# P3V3_PP5V_GESTION.net
KiCad netlist of a schematic drawn in Altium Designer
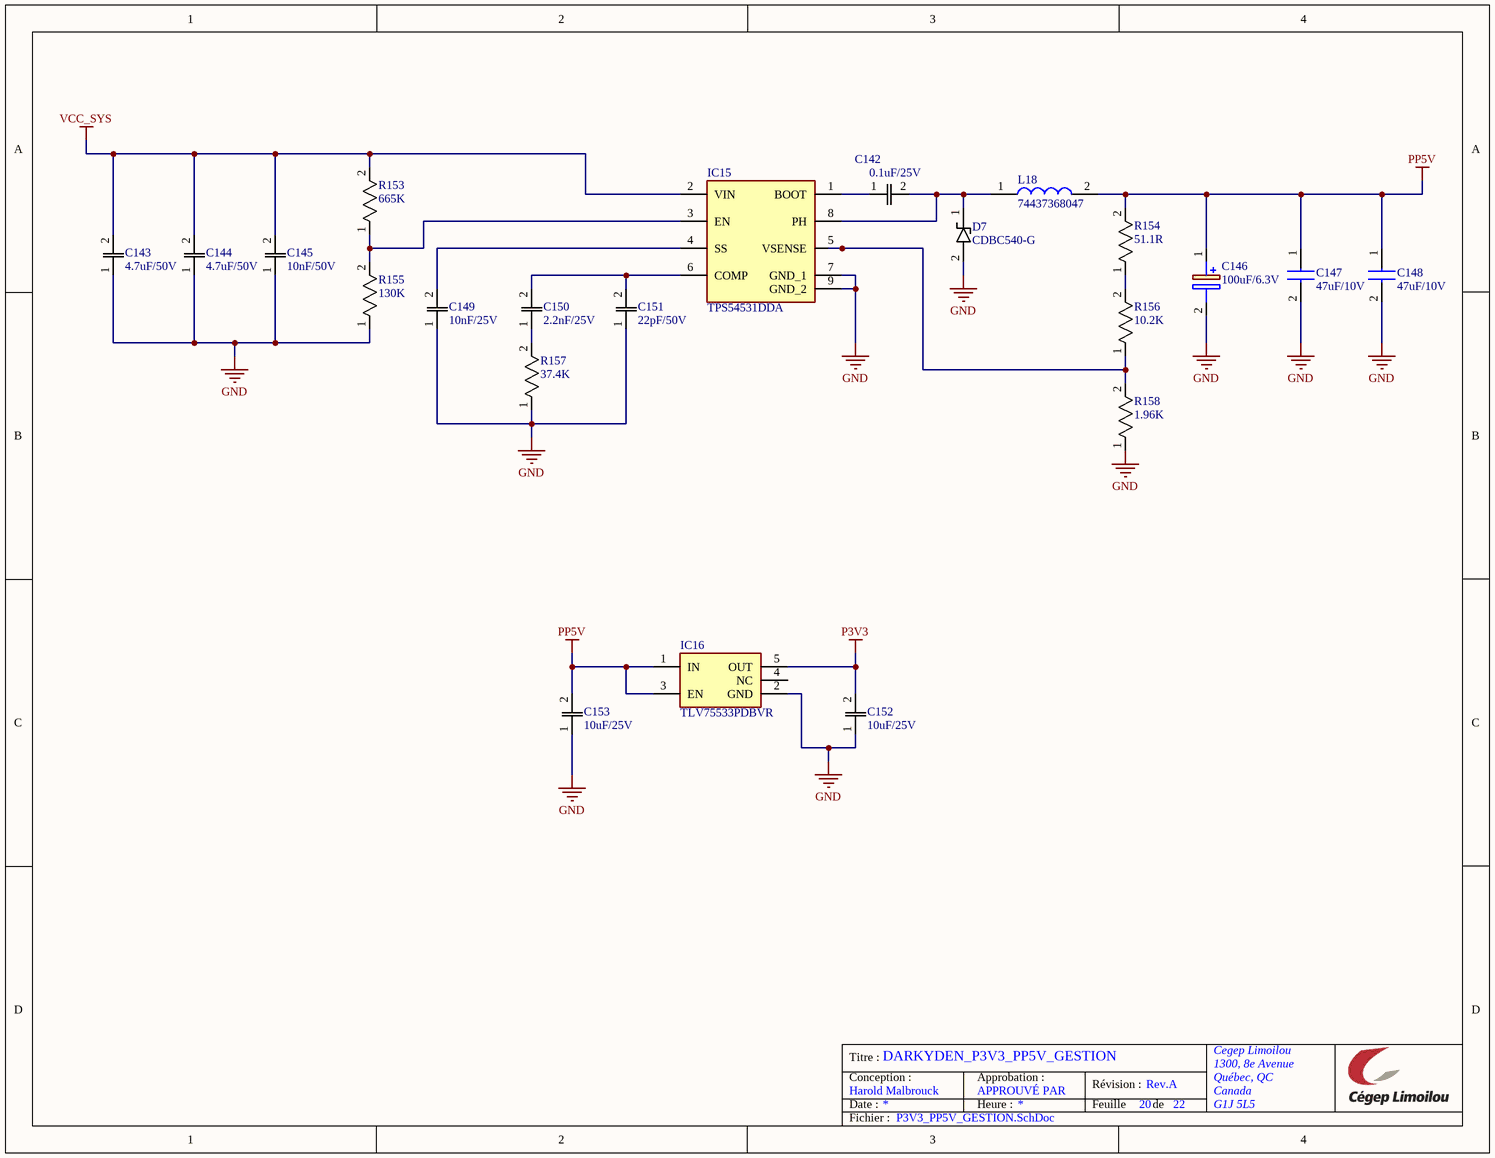
[diagram p0: P3V3_PP5V_GESTION.SchDoc]

(export (version "E")
  (design (tool "Eeschema 10.0.6"))
  (components
    (comp (ref "C142")
      (value "0.1uF/25V")
      (footprint "CAPC220145_88N_KEM")
      (description "0.1uF 25V X7R 10% SMD 0805 125C Plastic T/R")
      (fields
        (field (name "MANUFACTURER") "KEMET")
        (field (name "MANUFACTURER PART NUMBER") "C0805C104K3RACTU")
      )
      (libsource (lib "C0805C104K3RACTU") (part "C0805C104K3RACTU"))
    )
    (comp (ref "C143")
      (value "4.7uF/50V")
      (footprint "CAP_2012_TDK")
      (description "4.7uF/50V X5R 卤10% 0805 Multilayer Ceramic Capacitors MLCC - SMD/SMT ROHS")
      (fields
        (field (name "MANUFACTURER") "TDK")
        (field (name "MANUFACTURER PART NUMBER") "CGA4J3X5R1H475K125AB")
      )
      (libsource (lib "CGA4J3X5R1H475K125AB") (part "CGA4J3X5R1H475K125AB"))
    )
    (comp (ref "C144")
      (value "4.7uF/50V")
      (footprint "CAP_2012_TDK")
      (description "4.7uF/50V X5R 卤10% 0805 Multilayer Ceramic Capacitors MLCC - SMD/SMT ROHS")
      (fields
        (field (name "MANUFACTURER") "TDK")
        (field (name "MANUFACTURER PART NUMBER") "CGA4J3X5R1H475K125AB")
      )
      (libsource (lib "CGA4J3X5R1H475K125AB") (part "CGA4J3X5R1H475K125AB"))
    )
    (comp (ref "C145")
      (value "10nF/50V")
      (footprint "CAPC220145_88N_KEM")
      (description "10nF/50V X7R 0805 10%")
      (fields
        (field (name "MANUFACTURER") "KEMET")
        (field (name "MANUFACTURER PART NUMBER") "C0805C103K5RACTU")
      )
      (libsource (lib "C0805C103K5RACTU") (part "C0805C103K5RACTU"))
    )
    (comp (ref "C146")
      (value "100uF/6.3V")
      (footprint "SamacSys:T520B")
      (description "100uF / 6.3VDC B CASE 20%  Cap Tant Polymer SMD 3528-21 0.015 Ohm 105C T/R")
      (fields
        (field (name "MANUFACTURER_PART_NUMBER") "T520B107M006ATE015")
        (field (name "MOUSER PART NUMBER") "80-T520B107M6ATE15")
      )
      (libsource (lib "SamacSys") (part "T520B107M006ATE015"))
    )
    (comp (ref "C147")
      (value "47uF/10V")
      (footprint "SamacSys:CAPC3225X270N")
      (description "Multilayer Ceramic Capacitor, 47 uF, 10 V, ï¿½ 10%, X5R, 1210 [3225 Metric]")
      (fields
        (field (name "MANUFACTURER_PART_NUMBER") "GRM32ER61A476KE20L")
        (field (name "MOUSER PART NUMBER") "81-GRM32ER61A476KE20")
      )
      (libsource (lib "SamacSys") (part "GRM32ER61A476KE20L"))
    )
    (comp (ref "C148")
      (value "47uF/10V")
      (footprint "SamacSys:CAPC3225X270N")
      (description "Multilayer Ceramic Capacitor, 47 uF, 10 V, ï¿½ 10%, X5R, 1210 [3225 Metric]")
      (fields
        (field (name "MANUFACTURER_PART_NUMBER") "GRM32ER61A476KE20L")
        (field (name "MOUSER PART NUMBER") "81-GRM32ER61A476KE20")
      )
      (libsource (lib "SamacSys") (part "GRM32ER61A476KE20L"))
    )
    (comp (ref "C149")
      (value "10nF/25V")
      (footprint "SamacSys:C0805")
      (description "0.01uF 25V X7R 10% SMD 0805 125C Paper T/R")
      (fields
        (field (name "MANUFACTURER_PART_NUMBER") "C0805C103K3RACTU")
        (field (name "MOUSER PART NUMBER") "80-C0805C103K3R")
      )
      (libsource (lib "SamacSys") (part "C0805C103K3RACTU"))
    )
    (comp (ref "C150")
      (value "2.2nF/25V")
      (footprint "CAPC480350_110N_KEM")
      (description "2.2nF ±10% 25V Ceramic Capacitor C0G, NP0 0805 (2012 Metric)")
      (fields
        (field (name "MANUFACTURER") "KEMET")
        (field (name "MANUFACTURER PART NUMBER") "C0805C222K3GECTU")
      )
      (libsource (lib "C1812C222F1GACTU") (part "C0805C222K3GECTU"))
    )
    (comp (ref "C151")
      (value "22pF/50V")
      (footprint "CAPC220145_145N_KEM")
      (description "Cap Ceramic 22pF 50V X7R 5% Pad SMD 0805 125°C T/R")
      (fields
        (field (name "MANUFACTURER") "KEMET")
        (field (name "MANUFACTURER PART NUMBER") "C0805C220J5RACTU")
      )
      (libsource (lib "C0805C220J5RACTU") (part "C0805C220J5RACTU"))
    )
    (comp (ref "C152")
      (value "10uF/25V")
      (footprint "CAPC220145_88N_KEM")
      (description "10uF / 25 VDC, +85degC, X5R Dielec, +/-10% ¦ KEMET C0805C106K3PACTU 0805")
      (fields
        (field (name "MANUFACTURER") "KEMET")
        (field (name "MANUFACTURER PART NUMBER") "C0805C106K3PACTU")
      )
      (libsource (lib "C0805C106K3PACTU") (part "C0805C106K3PACTU"))
    )
    (comp (ref "C153")
      (value "10uF/25V")
      (footprint "CAPC220145_88N_KEM")
      (description "10uF / 25 VDC, +85degC, X5R Dielec, +/-10% ¦ KEMET C0805C106K3PACTU 0805")
      (fields
        (field (name "MANUFACTURER") "KEMET")
        (field (name "MANUFACTURER PART NUMBER") "C0805C106K3PACTU")
      )
      (libsource (lib "C0805C106K3PACTU") (part "C0805C106K3PACTU"))
    )
    (comp (ref "D7")
      (value "CDBC540-G")
      (footprint "SamacSys:DIOM8059X290N")
      (description "Schottky Diode 40V 5A 2-Pin DO-214AB (SMC) CDBC540-G SMT")
      (fields (field (name "MOUSER PART NUMBER") "750-CDBC540-G") (field (name "MANUFACTURER") "Comchip"))
      (libsource (lib "SamacSys") (part "CDBC540-G"))
    )
    (comp (ref "IC15")
      (value "TPS54531DDA")
      (footprint "SamacSys:SOIC127P600X170-9N")
      (fields (field (name "MOUSER PART NUMBER") "595-TPS54531DDA"))
      (libsource (lib "SamacSys") (part "TPS54531DDA"))
    )
    (comp (ref "IC16")
      (value "TLV75533PDBVR")
      (footprint "SamacSys:SOT95P280X145-5N")
      (description "500mA high-PSRR low-IQ low-dropout voltage regulator with enable 5-SOT-23 -40 to 125")
      (fields
        (field (name "MOUSER PART NUMBER") "595-TLV75533PDBVR")
        (field (name "MANUFACTURER") "Texas Instruments")
      )
      (libsource (lib "SamacSys") (part "TLV75533PDBVR"))
    )
    (comp (ref "L18")
      (value "74437368047")
      (footprint "SamacSys:WE-LHMI_104048")
      (fields
        (field (name "MOUSER PART NUMBER") "710-74437368047")
        (field (name "MANUFACTURER") "Wurth Electronics")
        (field (name "TOLERANCE") "20%")
      )
      (libsource (lib "SamacSys") (part "74437368047"))
    )
    (comp (ref "R153")
      (value "665K")
      (footprint "RC0603N_PAN")
      (description "665 kOhm, ± 1%, 100 mW, 0603 [1608 Metric], Thick Film, Precision")
      (fields
        (field (name "MANUFACTURER") "Panasonic")
        (field (name "MANUFACTURER PART NUMBER") "ERJ-3EKF6653V")
      )
      (libsource (lib "ERJ-3EKF6653V") (part "ERJ-3EKF6653V"))
    )
    (comp (ref "R154")
      (value "51.1R")
      (footprint "SamacSys:RESC1608X55N")
      (description "51.1 Ohm 1% 0.1W(1/10W) ±100ppm/C Pad SMD T/R Automotive AEC-Q200")
      (fields
        (field (name "MANUFACTURER_PART_NUMBER") "ERJ-3EKF51R1V")
        (field (name "MOUSER PART NUMBER") "667-ERJ-3EKF51R1V")
      )
      (libsource (lib "SamacSys") (part "ERJ-3EKF51R1V"))
    )
    (comp (ref "R155")
      (value "130K")
      (footprint "RC0603N_PAN")
      (description "130K Ohm 1% 0.1W Res Thick Film 0603 ±100ppm/°C Molded SMD Punched Carrier T/R")
      (fields
        (field (name "MANUFACTURER") "Panasonic")
        (field (name "MANUFACTURER PART NUMBER") "ERJ-3EKF1303V")
      )
      (libsource (lib "ERJ-3EKF1303V") (part "ERJ-3EKF1303V"))
    )
    (comp (ref "R156")
      (value "10.2K")
      (footprint "SamacSys:RESC1608X55N")
      (description "10.2 kOhm, ± 1%, 100 mW, 0603 [1608 Metric], Thick Film, Precision")
      (fields
        (field (name "MANUFACTURER_PART_NUMBER") "ERJ-3EKF1022V")
        (field (name "MOUSER PART NUMBER") "667-ERJ-3EKF1022V")
      )
      (libsource (lib "SamacSys") (part "ERJ-3EKF1022V"))
    )
    (comp (ref "R157")
      (value "37.4K")
      (footprint "RC0603N_PAN")
      (description "37.4K Ohm 1% 1/10W ±100ppm/°C Molded SMD Punched Carrier T/R")
      (fields
        (field (name "MANUFACTURER") "Panasonic")
        (field (name "MANUFACTURER PART NUMBER") "ERJ-3EKF3742V")
      )
      (libsource (lib "ERJ-3EKF3742V") (part "ERJ-3EKF3742V"))
    )
    (comp (ref "R158")
      (value "1.96K")
      (footprint "RC0603N_PAN")
      (description "1.96K Ohm 1% 1/10W ±100ppm/°C Molded SMD Punched Carrier T/R")
      (fields
        (field (name "MANUFACTURER") "Panasonic")
        (field (name "MANUFACTURER PART NUMBER") "ERJ-3EKF1961V")
      )
      (libsource (lib "ERJ-3EKF1961V") (part "ERJ-3EKF1961V"))
    )
  )
  (nets
    (net (code "1") (name "GND") (class "Default")
      (node (ref "C143") (pin "1") (pinfunction "1_1") (pintype "passive"))
      (node (ref "C144") (pin "1") (pinfunction "1_1") (pintype "passive"))
      (node (ref "C145") (pin "1") (pinfunction "1_1") (pintype "passive"))
      (node (ref "C146") (pin "2") (pinfunction "-_2") (pintype "passive"))
      (node (ref "C147") (pin "2") (pinfunction "2_2") (pintype "passive"))
      (node (ref "C148") (pin "2") (pinfunction "2_2") (pintype "passive"))
      (node (ref "C149") (pin "1") (pinfunction "1_1") (pintype "passive"))
      (node (ref "C151") (pin "1") (pinfunction "1_1") (pintype "passive"))
      (node (ref "C152") (pin "1") (pinfunction "1_1") (pintype "passive"))
      (node (ref "C153") (pin "1") (pinfunction "1_1") (pintype "passive"))
      (node (ref "D7") (pin "2") (pinfunction "A_2") (pintype "passive"))
      (node (ref "IC15") (pin "7") (pinfunction "GND_1_7") (pintype "passive"))
      (node (ref "IC15") (pin "9") (pinfunction "GND_2_9") (pintype "passive"))
      (node (ref "IC16") (pin "2") (pinfunction "GND_2") (pintype "passive"))
      (node (ref "R155") (pin "1") (pinfunction "1_1") (pintype "passive"))
      (node (ref "R157") (pin "1") (pinfunction "1_1") (pintype "passive"))
      (node (ref "R158") (pin "1") (pinfunction "1_1") (pintype "passive"))
    )
    (net (code "2") (name "Net-(C150-Pad1)") (class "Default")
      (node (ref "C150") (pin "1") (pinfunction "1_1") (pintype "passive"))
      (node (ref "R157") (pin "2") (pinfunction "2_2") (pintype "passive"))
    )
    (net (code "3") (name "Net-(D7-K)") (class "Default")
      (node (ref "C142") (pin "2") (pinfunction "2_2") (pintype "passive"))
      (node (ref "D7") (pin "1") (pinfunction "K_1") (pintype "passive"))
      (node (ref "IC15") (pin "8") (pinfunction "PH_8") (pintype "passive"))
      (node (ref "L18") (pin "1") (pinfunction "1_1") (pintype "passive"))
    )
    (net (code "4") (name "Net-(IC15-BOOT)") (class "Default")
      (node (ref "C142") (pin "1") (pinfunction "1_1") (pintype "passive"))
      (node (ref "IC15") (pin "1") (pinfunction "BOOT_1") (pintype "passive"))
    )
    (net (code "5") (name "Net-(IC15-COMP)") (class "Default")
      (node (ref "C150") (pin "2") (pinfunction "2_2") (pintype "passive"))
      (node (ref "C151") (pin "2") (pinfunction "2_2") (pintype "passive"))
      (node (ref "IC15") (pin "6") (pinfunction "COMP_6") (pintype "passive"))
    )
    (net (code "6") (name "Net-(IC15-EN)") (class "Default")
      (node (ref "IC15") (pin "3") (pinfunction "EN_3") (pintype "passive"))
      (node (ref "R153") (pin "1") (pinfunction "1_1") (pintype "passive"))
      (node (ref "R155") (pin "2") (pinfunction "2_2") (pintype "passive"))
    )
    (net (code "7") (name "Net-(IC15-SS)") (class "Default")
      (node (ref "C149") (pin "2") (pinfunction "2_2") (pintype "passive"))
      (node (ref "IC15") (pin "4") (pinfunction "SS_4") (pintype "passive"))
    )
    (net (code "8") (name "Net-(IC15-VSENSE)") (class "Default")
      (node (ref "IC15") (pin "5") (pinfunction "VSENSE_5") (pintype "passive"))
      (node (ref "R156") (pin "1") (pinfunction "1_1") (pintype "passive"))
      (node (ref "R158") (pin "2") (pinfunction "2_2") (pintype "passive"))
    )
    (net (code "9") (name "Net-(R154-Pad1)") (class "Default")
      (node (ref "R154") (pin "1") (pinfunction "1_1") (pintype "passive"))
      (node (ref "R156") (pin "2") (pinfunction "2_2") (pintype "passive"))
    )
    (net (code "10") (name "P3V3") (class "Default")
      (node (ref "C152") (pin "2") (pinfunction "2_2") (pintype "passive"))
      (node (ref "IC16") (pin "5") (pinfunction "OUT_5") (pintype "passive"))
    )
    (net (code "11") (name "PP5V") (class "Default")
      (node (ref "C146") (pin "1") (pinfunction "+_1") (pintype "passive"))
      (node (ref "C147") (pin "1") (pinfunction "1_1") (pintype "passive"))
      (node (ref "C148") (pin "1") (pinfunction "1_1") (pintype "passive"))
      (node (ref "C153") (pin "2") (pinfunction "2_2") (pintype "passive"))
      (node (ref "IC16") (pin "1") (pinfunction "IN_1") (pintype "passive"))
      (node (ref "IC16") (pin "3") (pinfunction "EN_3") (pintype "passive"))
      (node (ref "L18") (pin "2") (pinfunction "2_2") (pintype "passive"))
      (node (ref "R154") (pin "2") (pinfunction "2_2") (pintype "passive"))
    )
    (net (code "12") (name "VCC_SYS") (class "Default")
      (node (ref "C143") (pin "2") (pinfunction "2_2") (pintype "passive"))
      (node (ref "C144") (pin "2") (pinfunction "2_2") (pintype "passive"))
      (node (ref "C145") (pin "2") (pinfunction "2_2") (pintype "passive"))
      (node (ref "IC15") (pin "2") (pinfunction "VIN_2") (pintype "passive"))
      (node (ref "R153") (pin "2") (pinfunction "2_2") (pintype "passive"))
    )
    (net (code "13") (name "unconnected-(IC16-NC-Pad4)") (class "Default")
      (node (ref "IC16") (pin "4") (pinfunction "NC_4") (pintype "passive"))
    )
  )
)
